# Proiect_v64.net
KiCad netlist of a schematic drawn in EAGLE
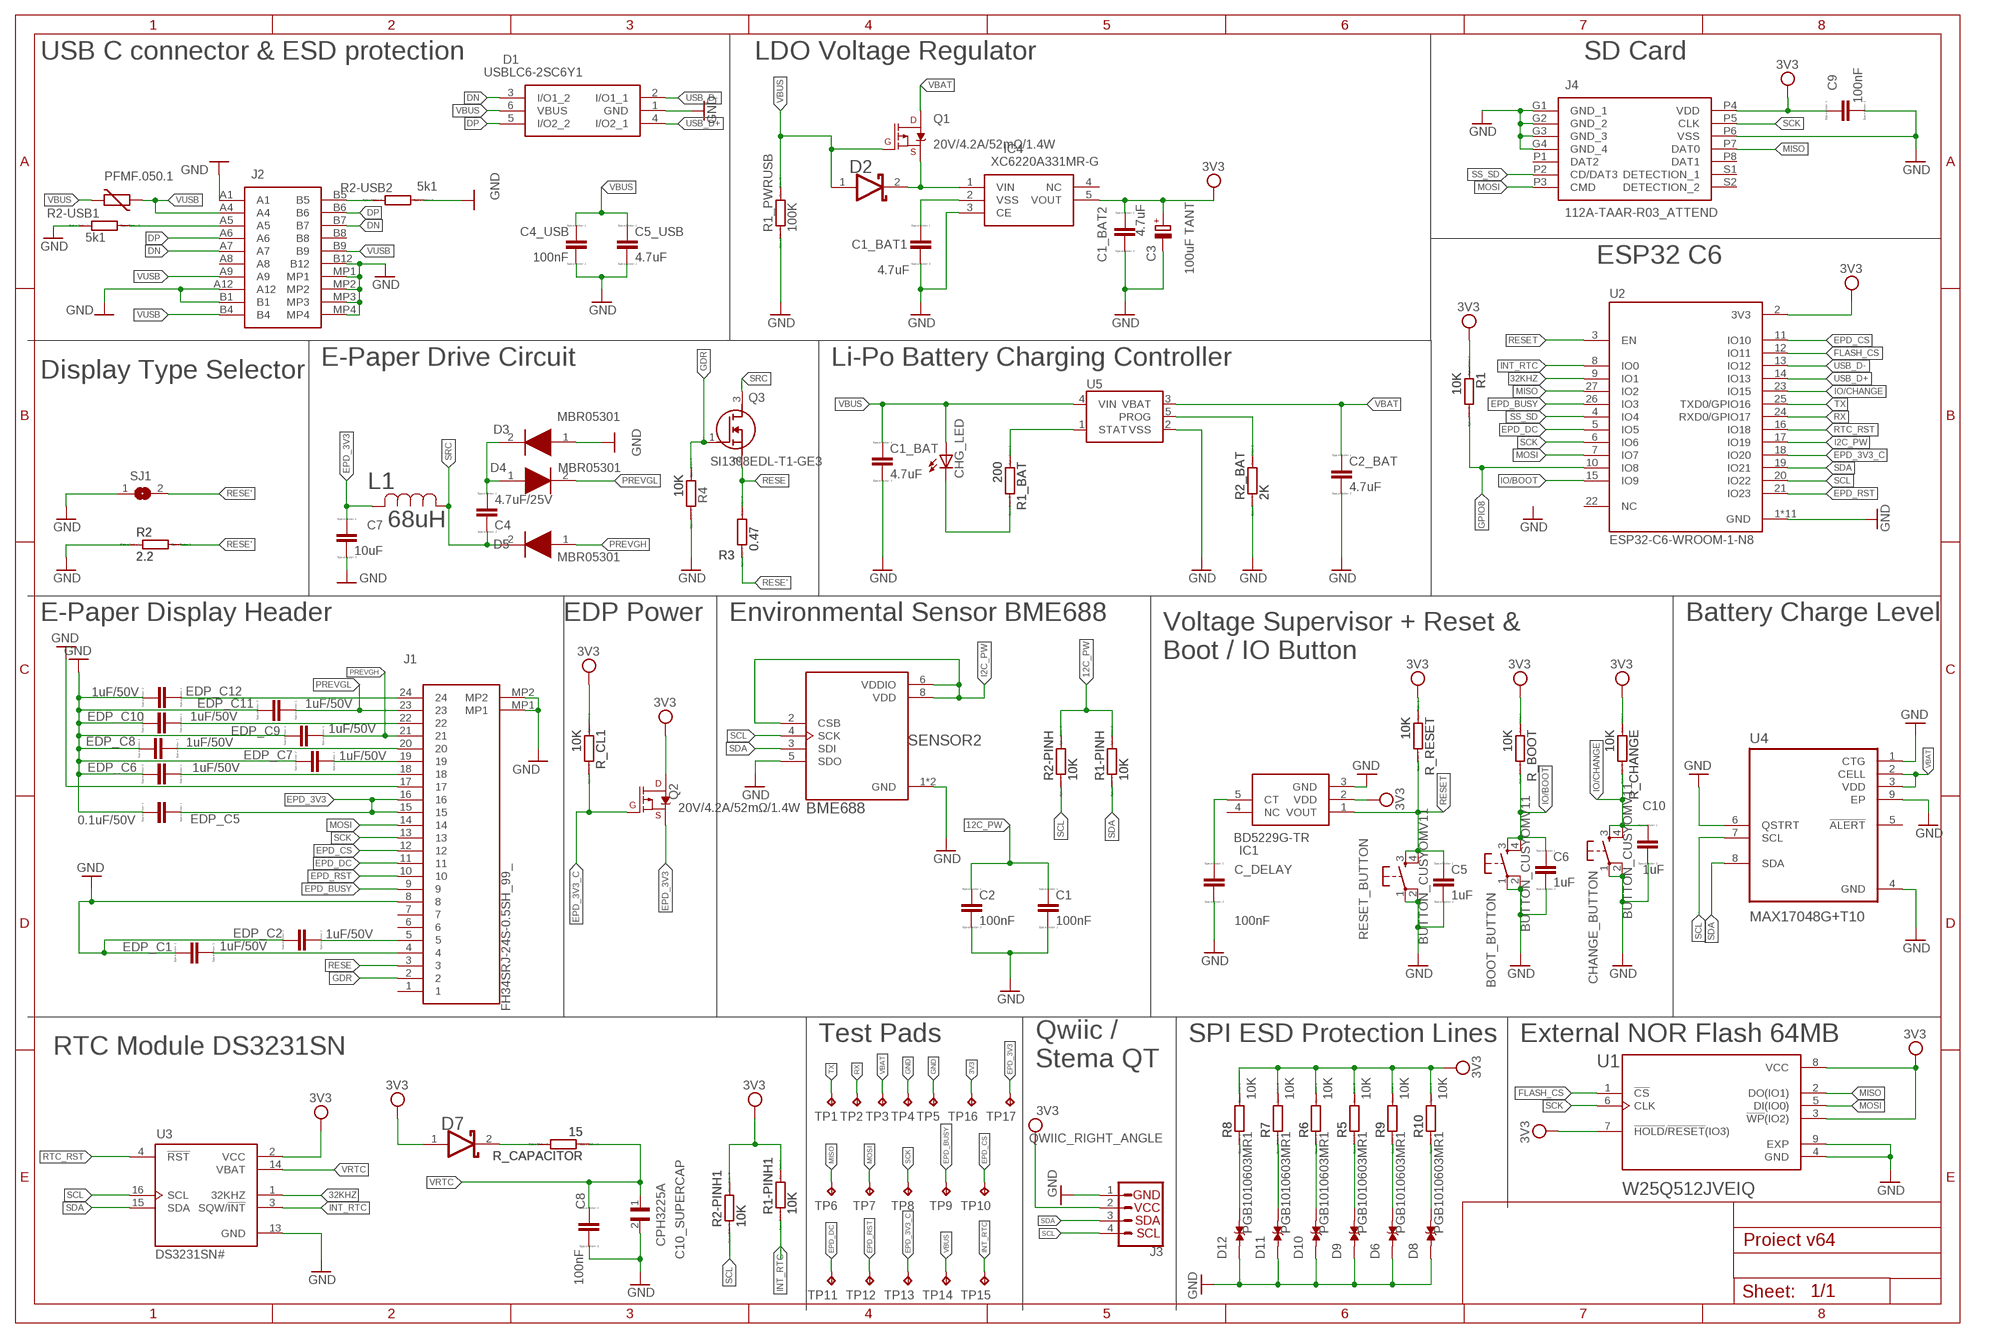
[diagram p0: schematic, sheet 1]

(export (version "E")
  (design (tool "Eeschema 10.0.6"))
  (components
    (comp (ref "BOOT_BUTTON")
      (value "BUTTON_CUSYOMV11")
      (footprint "eagle-import:MYBUTTON")
      (libsource (lib "eagle-import") (part "BUTTON_CUSYOMV11"))
    )
    (comp (ref "C1")
      (value "100nF")
      (footprint "eagle-import:ESP32_WROVER_EAGLE-LTSPICE_C0402")
      (libsource (lib "eagle-import") (part "ESP32_WROVER_EAGLE-LTSPICE_C"))
    )
    (comp (ref "C1_BAT")
      (value "4.7uF")
      (footprint "eagle-import:ESP32_WROVER_EAGLE-LTSPICE_C0402")
      (libsource (lib "eagle-import") (part "ESP32_WROVER_EAGLE-LTSPICE_C"))
    )
    (comp (ref "C1_BAT1")
      (value "4.7uF")
      (footprint "eagle-import:ESP32_WROVER_EAGLE-LTSPICE_C0402")
      (libsource (lib "eagle-import") (part "ESP32_WROVER_EAGLE-LTSPICE_C"))
    )
    (comp (ref "C1_BAT2")
      (value "4.7uF")
      (footprint "eagle-import:ESP32_WROVER_EAGLE-LTSPICE_C0402")
      (libsource (lib "eagle-import") (part "ESP32_WROVER_EAGLE-LTSPICE_C"))
    )
    (comp (ref "C2")
      (value "100nF")
      (footprint "eagle-import:ESP32_WROVER_EAGLE-LTSPICE_C0402")
      (libsource (lib "eagle-import") (part "ESP32_WROVER_EAGLE-LTSPICE_C"))
    )
    (comp (ref "C2_BAT")
      (value "4.7uF")
      (footprint "eagle-import:ESP32_WROVER_EAGLE-LTSPICE_C0402")
      (libsource (lib "eagle-import") (part "ESP32_WROVER_EAGLE-LTSPICE_C"))
    )
    (comp (ref "C3")
      (value "100uF TANT")
      (footprint "eagle-import:RCL_CT3528")
      (libsource (lib "eagle-import") (part "RCL_CPOL-EUCT3528"))
    )
    (comp (ref "C4")
      (value "4.7uF/25V")
      (footprint "eagle-import:ESP32_WROVER_EAGLE-LTSPICE_C0402")
      (libsource (lib "eagle-import") (part "ESP32_WROVER_EAGLE-LTSPICE_C"))
    )
    (comp (ref "C4_USB")
      (value "100nF")
      (footprint "eagle-import:ESP32_WROVER_EAGLE-LTSPICE_C0402")
      (libsource (lib "eagle-import") (part "ESP32_WROVER_EAGLE-LTSPICE_C"))
    )
    (comp (ref "C5")
      (value "1uF")
      (footprint "eagle-import:ESP32_WROVER_EAGLE-LTSPICE_C0402")
      (libsource (lib "eagle-import") (part "ESP32_WROVER_EAGLE-LTSPICE_C"))
    )
    (comp (ref "C5_USB")
      (value "4.7uF")
      (footprint "eagle-import:ESP32_WROVER_EAGLE-LTSPICE_C0402")
      (libsource (lib "eagle-import") (part "ESP32_WROVER_EAGLE-LTSPICE_C"))
    )
    (comp (ref "C6")
      (value "1uF")
      (footprint "eagle-import:ESP32_WROVER_EAGLE-LTSPICE_C0402")
      (libsource (lib "eagle-import") (part "ESP32_WROVER_EAGLE-LTSPICE_C"))
    )
    (comp (ref "C7")
      (value "10uF")
      (footprint "eagle-import:ESP32_WROVER_EAGLE-LTSPICE_C0402")
      (libsource (lib "eagle-import") (part "ESP32_WROVER_EAGLE-LTSPICE_C"))
    )
    (comp (ref "C8")
      (value "100nF")
      (footprint "eagle-import:ESP32_WROVER_EAGLE-LTSPICE_C0402")
      (libsource (lib "eagle-import") (part "ESP32_WROVER_EAGLE-LTSPICE_C"))
    )
    (comp (ref "C9")
      (value "100nF")
      (footprint "eagle-import:ESP32_WROVER_EAGLE-LTSPICE_C0402")
      (libsource (lib "eagle-import") (part "ESP32_WROVER_EAGLE-LTSPICE_C"))
    )
    (comp (ref "C10")
      (value "1uF")
      (footprint "eagle-import:ESP32_WROVER_EAGLE-LTSPICE_C0402")
      (libsource (lib "eagle-import") (part "ESP32_WROVER_EAGLE-LTSPICE_C"))
    )
    (comp (ref "C10_SUPERCAP")
      (value "CPH3225A")
      (footprint "eagle-import:CAPCP3225X100N")
      (fields (field (name "MF") "Seiko Instruments"))
      (libsource (lib "eagle-import") (part "CPH3225A"))
    )
    (comp (ref "CHANGE_BUTTON")
      (value "BUTTON_CUSYOMV11")
      (footprint "eagle-import:MYBUTTON")
      (libsource (lib "eagle-import") (part "BUTTON_CUSYOMV11"))
    )
    (comp (ref "CHG_LED")
      (value "1")
      (footprint "eagle-import:ADAFRUIT_CHIP-LED0603")
      (libsource (lib "eagle-import") (part "ADAFRUIT_LEDCHIP-LED0603"))
    )
    (comp (ref "C_DELAY")
      (value "100nF")
      (footprint "eagle-import:ESP32_WROVER_EAGLE-LTSPICE_C0402")
      (libsource (lib "eagle-import") (part "ESP32_WROVER_EAGLE-LTSPICE_C"))
    )
    (comp (ref "D1")
      (value "USBLC6-2SC6Y1")
      (footprint "eagle-import:SOT95P280X145-6N")
      (libsource (lib "eagle-import") (part "USBLC6-2SC6Y1"))
    )
    (comp (ref "D2")
      (value "ESP32_WROVER_AVX---SD0805S020S1R0_AVX_SD0805S020S1R0_0_0")
      (footprint "eagle-import:ESP32_WROVER_AVX---SD0805S020S1R0_AVX_SD0805S020S1R0_0")
      (libsource (lib "eagle-import") (part "ESP32_WROVER_AVX---SD0805S020S1R0_AVX_SD0805S020S1R0_0_0"))
    )
    (comp (ref "D3")
      (value "MBR05301")
      (footprint "eagle-import:SOD3716X135N")
      (libsource (lib "eagle-import") (part "MBR05301"))
    )
    (comp (ref "D4")
      (value "MBR05301")
      (footprint "eagle-import:SOD3716X135N")
      (libsource (lib "eagle-import") (part "MBR05301"))
    )
    (comp (ref "D5")
      (value "MBR05301")
      (footprint "eagle-import:SOD3716X135N")
      (libsource (lib "eagle-import") (part "MBR05301"))
    )
    (comp (ref "D6")
      (value "PGB1010603MR1")
      (footprint "eagle-import:DIOC1608X36N")
      (libsource (lib "eagle-import") (part "PGB1010603MR1"))
    )
    (comp (ref "D7")
      (value "SD805S020S1R0")
      (footprint "eagle-import:ESP32_WROVER_AVX---SD0805S020S1R0_AVX_SD0805S020S1R0_0")
      (libsource (lib "eagle-import") (part "ESP32_WROVER_AVX---SD0805S020S1R0_AVX_SD0805S020S1R0_0_0"))
    )
    (comp (ref "D8")
      (value "PGB1010603MR1")
      (footprint "eagle-import:DIOC1608X36N")
      (libsource (lib "eagle-import") (part "PGB1010603MR1"))
    )
    (comp (ref "D9")
      (value "PGB1010603MR1")
      (footprint "eagle-import:DIOC1608X36N")
      (libsource (lib "eagle-import") (part "PGB1010603MR1"))
    )
    (comp (ref "D10")
      (value "PGB1010603MR1")
      (footprint "eagle-import:DIOC1608X36N")
      (libsource (lib "eagle-import") (part "PGB1010603MR1"))
    )
    (comp (ref "D11")
      (value "PGB1010603MR1")
      (footprint "eagle-import:DIOC1608X36N")
      (libsource (lib "eagle-import") (part "PGB1010603MR1"))
    )
    (comp (ref "D12")
      (value "PGB1010603MR1")
      (footprint "eagle-import:DIOC1608X36N")
      (libsource (lib "eagle-import") (part "PGB1010603MR1"))
    )
    (comp (ref "EDP_C1")
      (value "1uF/50V")
      (footprint "eagle-import:ESP32_WROVER_EAGLE-LTSPICE_C0402")
      (libsource (lib "eagle-import") (part "ESP32_WROVER_EAGLE-LTSPICE_C"))
    )
    (comp (ref "EDP_C2")
      (value "1uF/50V")
      (footprint "eagle-import:ESP32_WROVER_EAGLE-LTSPICE_C0402")
      (libsource (lib "eagle-import") (part "ESP32_WROVER_EAGLE-LTSPICE_C"))
    )
    (comp (ref "EDP_C5")
      (value "0.1uF/50V")
      (footprint "eagle-import:ESP32_WROVER_EAGLE-LTSPICE_C0402")
      (libsource (lib "eagle-import") (part "ESP32_WROVER_EAGLE-LTSPICE_C"))
    )
    (comp (ref "EDP_C6")
      (value "1uF/50V")
      (footprint "eagle-import:ESP32_WROVER_EAGLE-LTSPICE_C0402")
      (libsource (lib "eagle-import") (part "ESP32_WROVER_EAGLE-LTSPICE_C"))
    )
    (comp (ref "EDP_C7")
      (value "1uF/50V")
      (footprint "eagle-import:ESP32_WROVER_EAGLE-LTSPICE_C0402")
      (libsource (lib "eagle-import") (part "ESP32_WROVER_EAGLE-LTSPICE_C"))
    )
    (comp (ref "EDP_C8")
      (value "1uF/50V")
      (footprint "eagle-import:ESP32_WROVER_EAGLE-LTSPICE_C0402")
      (libsource (lib "eagle-import") (part "ESP32_WROVER_EAGLE-LTSPICE_C"))
    )
    (comp (ref "EDP_C9")
      (value "1uF/50V")
      (footprint "eagle-import:ESP32_WROVER_EAGLE-LTSPICE_C0402")
      (libsource (lib "eagle-import") (part "ESP32_WROVER_EAGLE-LTSPICE_C"))
    )
    (comp (ref "EDP_C10")
      (value "1uF/50V")
      (footprint "eagle-import:ESP32_WROVER_EAGLE-LTSPICE_C0402")
      (libsource (lib "eagle-import") (part "ESP32_WROVER_EAGLE-LTSPICE_C"))
    )
    (comp (ref "EDP_C11")
      (value "1uF/50V")
      (footprint "eagle-import:ESP32_WROVER_EAGLE-LTSPICE_C0402")
      (libsource (lib "eagle-import") (part "ESP32_WROVER_EAGLE-LTSPICE_C"))
    )
    (comp (ref "EDP_C12")
      (value "1uF/50V")
      (footprint "eagle-import:ESP32_WROVER_EAGLE-LTSPICE_C0402")
      (libsource (lib "eagle-import") (part "ESP32_WROVER_EAGLE-LTSPICE_C"))
    )
    (comp (ref "IC1")
      (value "BD5229G-TR")
      (footprint "eagle-import:SOT95P280X125-5N")
      (fields (field (name "MOUSER_PART_NUMBER") "755-BD5229G-TR"))
      (libsource (lib "eagle-import") (part "BD5229G-TR"))
    )
    (comp (ref "IC4")
      (value "XC6220A331MR-G")
      (footprint "eagle-import:SOT95P280X120-5N")
      (fields (field (name "MOUSER_PART_NUMBER") "865-XC6220A331MR-G"))
      (libsource (lib "eagle-import") (part "XC6220A331MR-G"))
    )
    (comp (ref "J1")
      (value "FH34SRJ-24S-0.5SH_99_")
      (footprint "eagle-import:FH34SRJ24S05SH99")
      (fields
        (field (name "MANUFACTURER_PART_NUMBER") "FH34SRJ-24S-0.5SH(99)")
        (field (name "MOUSER_PART_NUMBER") "798-FH34SRJ24S05SH99")
      )
      (libsource (lib "eagle-import") (part "FH34SRJ-24S-0.5SH_99_"))
    )
    (comp (ref "J2")
      (value "SAMACSYS_PARTS_USB4110-GF-A")
      (footprint "eagle-import:SAMACSYS_PARTS_USB4110GFA")
      (fields
        (field (name "MANUFACTURER_PART_NUMBER") "USB4110-GF-A")
        (field (name "MOUSER_PART_NUMBER") "640-USB4110-GF-A")
      )
      (libsource (lib "eagle-import") (part "SAMACSYS_PARTS_USB4110-GF-A"))
    )
    (comp (ref "J3")
      (value "QWIIC_RIGHT_ANGLE")
      (footprint "eagle-import:JST04_1MM_RA")
      (libsource (lib "eagle-import") (part "QWIIC_CONNECTORJS-1MM"))
    )
    (comp (ref "J4")
      (value "112A-TAAR-R03_ATTEND")
      (footprint "eagle-import:112ATAARR03ATTEND")
      (fields (field (name "MANUFACTURER_PART_NUMBER") "112A-TAAR-R03 ATTEND"))
      (libsource (lib "eagle-import") (part "112A-TAAR-R03_ATTEND"))
    )
    (comp (ref "L1")
      (value "68uH")
      (footprint "eagle-import:IND_4828-WE-TPC_WRE")
      (fields
        (field (name "MANUFACTURER_PART_NUMBER") "744043680")
        (field (name "COPYRIGHT") "Copyright (C) 2024 Ultra Librarian. All rights reserved.")
      )
      (libsource (lib "eagle-import") (part "744043680IND_4828-WE-TPC_WRE"))
    )
    (comp (ref "PFMF.050.1")
      (value "ESP32C6_VARISTORCN1812")
      (footprint "eagle-import:ESP32C6_VARISTOR_CT_CN1812")
      (libsource (lib "eagle-import") (part "ESP32C6_VARISTORCN1812"))
    )
    (comp (ref "Q1")
      (value "20V/4.2A/52mΩ/1.4W")
      (footprint "eagle-import:ESP32_WROVER_SPARKFUN-DISCRETESEMI_SOT23-3")
      (libsource (lib "eagle-import") (part "ESP32_WROVER_SPARKFUN-DISCRETESEMI_MOSFET_PCH"))
    )
    (comp (ref "Q2")
      (value "20V/4.2A/52mΩ/1.4W")
      (footprint "eagle-import:ESP32_WROVER_SPARKFUN-DISCRETESEMI_SOT23-3")
      (libsource (lib "eagle-import") (part "ESP32_WROVER_SPARKFUN-DISCRETESEMI_MOSFET_PCH"))
    )
    (comp (ref "Q3")
      (value "SI1308EDL-T1-GE3")
      (footprint "eagle-import:SOT65P210X110-3N")
      (fields (field (name "MF") "Vishay Siliconix"))
      (libsource (lib "eagle-import") (part "SI1308EDL-T1-GE3"))
    )
    (comp (ref "R1")
      (value "10K")
      (footprint "eagle-import:ESP32_WROVER_EAGLE-LTSPICE_R0402")
      (libsource (lib "eagle-import") (part "ESP32_WROVER_EAGLE-LTSPICE_R"))
    )
    (comp (ref "R1-PINH")
      (value "10K")
      (footprint "eagle-import:ESP32_WROVER_EAGLE-LTSPICE_R0402")
      (libsource (lib "eagle-import") (part "ESP32_WROVER_EAGLE-LTSPICE_R"))
    )
    (comp (ref "R1-PINH1")
      (value "10K")
      (footprint "eagle-import:ESP32_WROVER_EAGLE-LTSPICE_R0402")
      (libsource (lib "eagle-import") (part "ESP32_WROVER_EAGLE-LTSPICE_R"))
    )
    (comp (ref "R1_BAT")
      (value "200")
      (footprint "eagle-import:ESP32_WROVER_EAGLE-LTSPICE_R0402")
      (libsource (lib "eagle-import") (part "ESP32_WROVER_EAGLE-LTSPICE_R"))
    )
    (comp (ref "R1_PWRUSB")
      (value "100K")
      (footprint "eagle-import:ESP32_WROVER_EAGLE-LTSPICE_R0402")
      (libsource (lib "eagle-import") (part "ESP32_WROVER_EAGLE-LTSPICE_R"))
    )
    (comp (ref "R2")
      (value "2.2")
      (footprint "eagle-import:ESP32_WROVER_EAGLE-LTSPICE_R0402")
      (libsource (lib "eagle-import") (part "ESP32_WROVER_EAGLE-LTSPICE_R"))
    )
    (comp (ref "R2-PINH")
      (value "10K")
      (footprint "eagle-import:ESP32_WROVER_EAGLE-LTSPICE_R0402")
      (libsource (lib "eagle-import") (part "ESP32_WROVER_EAGLE-LTSPICE_R"))
    )
    (comp (ref "R2-PINH1")
      (value "10K")
      (footprint "eagle-import:ESP32_WROVER_EAGLE-LTSPICE_R0402")
      (libsource (lib "eagle-import") (part "ESP32_WROVER_EAGLE-LTSPICE_R"))
    )
    (comp (ref "R2-USB1")
      (value "5k1")
      (footprint "eagle-import:ESP32_WROVER_EAGLE-LTSPICE_R0402")
      (libsource (lib "eagle-import") (part "ESP32_WROVER_EAGLE-LTSPICE_R"))
    )
    (comp (ref "R2-USB2")
      (value "5k1")
      (footprint "eagle-import:ESP32_WROVER_EAGLE-LTSPICE_R0402")
      (libsource (lib "eagle-import") (part "ESP32_WROVER_EAGLE-LTSPICE_R"))
    )
    (comp (ref "R2_BAT")
      (value "2K")
      (footprint "eagle-import:ESP32_WROVER_EAGLE-LTSPICE_R0402")
      (libsource (lib "eagle-import") (part "ESP32_WROVER_EAGLE-LTSPICE_R"))
    )
    (comp (ref "R3")
      (value "0.47")
      (footprint "eagle-import:ESP32_WROVER_EAGLE-LTSPICE_R0402")
      (libsource (lib "eagle-import") (part "ESP32_WROVER_EAGLE-LTSPICE_R"))
    )
    (comp (ref "R4")
      (value "10K")
      (footprint "eagle-import:ESP32_WROVER_EAGLE-LTSPICE_R0402")
      (libsource (lib "eagle-import") (part "ESP32_WROVER_EAGLE-LTSPICE_R"))
    )
    (comp (ref "R5")
      (value "10K")
      (footprint "eagle-import:ESP32_WROVER_EAGLE-LTSPICE_R0402")
      (libsource (lib "eagle-import") (part "ESP32_WROVER_EAGLE-LTSPICE_R"))
    )
    (comp (ref "R6")
      (value "10K")
      (footprint "eagle-import:ESP32_WROVER_EAGLE-LTSPICE_R0402")
      (libsource (lib "eagle-import") (part "ESP32_WROVER_EAGLE-LTSPICE_R"))
    )
    (comp (ref "R7")
      (value "10K")
      (footprint "eagle-import:ESP32_WROVER_EAGLE-LTSPICE_R0402")
      (libsource (lib "eagle-import") (part "ESP32_WROVER_EAGLE-LTSPICE_R"))
    )
    (comp (ref "R8")
      (value "10K")
      (footprint "eagle-import:ESP32_WROVER_EAGLE-LTSPICE_R0402")
      (libsource (lib "eagle-import") (part "ESP32_WROVER_EAGLE-LTSPICE_R"))
    )
    (comp (ref "R9")
      (value "10K")
      (footprint "eagle-import:ESP32_WROVER_EAGLE-LTSPICE_R0402")
      (libsource (lib "eagle-import") (part "ESP32_WROVER_EAGLE-LTSPICE_R"))
    )
    (comp (ref "R10")
      (value "10K")
      (footprint "eagle-import:ESP32_WROVER_EAGLE-LTSPICE_R0402")
      (libsource (lib "eagle-import") (part "ESP32_WROVER_EAGLE-LTSPICE_R"))
    )
    (comp (ref "RESET_BUTTON")
      (value "BUTTON_CUSYOMV11")
      (footprint "eagle-import:MYBUTTON")
      (libsource (lib "eagle-import") (part "BUTTON_CUSYOMV11"))
    )
    (comp (ref "R_BOOT")
      (value "10K")
      (footprint "eagle-import:ESP32_WROVER_EAGLE-LTSPICE_R0402")
      (libsource (lib "eagle-import") (part "ESP32_WROVER_EAGLE-LTSPICE_R"))
    )
    (comp (ref "R_CAPACITOR")
      (value "15")
      (footprint "eagle-import:ESP32_WROVER_EAGLE-LTSPICE_R0402")
      (libsource (lib "eagle-import") (part "ESP32_WROVER_EAGLE-LTSPICE_R"))
    )
    (comp (ref "R_CHANGE")
      (value "10K")
      (footprint "eagle-import:ESP32_WROVER_EAGLE-LTSPICE_R0402")
      (libsource (lib "eagle-import") (part "ESP32_WROVER_EAGLE-LTSPICE_R"))
    )
    (comp (ref "R_CL1")
      (value "10K")
      (footprint "eagle-import:ESP32_WROVER_EAGLE-LTSPICE_R0402")
      (libsource (lib "eagle-import") (part "ESP32_WROVER_EAGLE-LTSPICE_R"))
    )
    (comp (ref "R_RESET")
      (value "10K")
      (footprint "eagle-import:ESP32_WROVER_EAGLE-LTSPICE_R0402")
      (libsource (lib "eagle-import") (part "ESP32_WROVER_EAGLE-LTSPICE_R"))
    )
    (comp (ref "SENSOR2")
      (value "BME688")
      (footprint "eagle-import:ESP32_WROVER_BME680_PSON80P300X300X100-8N")
      (fields (field (name "MF") "Bosch Sensortec") (field (name "MP") "BME680"))
      (libsource (lib "eagle-import") (part "ESP32_WROVER_BME680_BME680"))
    )
    (comp (ref "SJ1") (value "1") (footprint "eagle-import:SJ") (libsource (lib "eagle-import") (part "SJ")))
    (comp (ref "TP1")
      (value "TP")
      (footprint "eagle-import:TP20R")
      (libsource (lib "eagle-import") (part "TP"))
    )
    (comp (ref "TP2")
      (value "TP")
      (footprint "eagle-import:TP20R")
      (libsource (lib "eagle-import") (part "TP"))
    )
    (comp (ref "TP3")
      (value "TP")
      (footprint "eagle-import:TP20R")
      (libsource (lib "eagle-import") (part "TP"))
    )
    (comp (ref "TP4")
      (value "TP")
      (footprint "eagle-import:TP20R")
      (libsource (lib "eagle-import") (part "TP"))
    )
    (comp (ref "TP5")
      (value "TP")
      (footprint "eagle-import:TP20R")
      (libsource (lib "eagle-import") (part "TP"))
    )
    (comp (ref "TP6")
      (value "TP")
      (footprint "eagle-import:TP20R")
      (libsource (lib "eagle-import") (part "TP"))
    )
    (comp (ref "TP7")
      (value "TP")
      (footprint "eagle-import:TP20R")
      (libsource (lib "eagle-import") (part "TP"))
    )
    (comp (ref "TP8")
      (value "TP")
      (footprint "eagle-import:TP20R")
      (libsource (lib "eagle-import") (part "TP"))
    )
    (comp (ref "TP9")
      (value "TP")
      (footprint "eagle-import:TP20R")
      (libsource (lib "eagle-import") (part "TP"))
    )
    (comp (ref "TP10")
      (value "TP")
      (footprint "eagle-import:TP20R")
      (libsource (lib "eagle-import") (part "TP"))
    )
    (comp (ref "TP11")
      (value "TP")
      (footprint "eagle-import:TP20R")
      (libsource (lib "eagle-import") (part "TP"))
    )
    (comp (ref "TP12")
      (value "TP")
      (footprint "eagle-import:TP20R")
      (libsource (lib "eagle-import") (part "TP"))
    )
    (comp (ref "TP13")
      (value "TP")
      (footprint "eagle-import:TP20R")
      (libsource (lib "eagle-import") (part "TP"))
    )
    (comp (ref "TP14")
      (value "TP")
      (footprint "eagle-import:TP20R")
      (libsource (lib "eagle-import") (part "TP"))
    )
    (comp (ref "TP15")
      (value "TP")
      (footprint "eagle-import:TP20R")
      (libsource (lib "eagle-import") (part "TP"))
    )
    (comp (ref "TP16")
      (value "TP")
      (footprint "eagle-import:TP20R")
      (libsource (lib "eagle-import") (part "TP"))
    )
    (comp (ref "TP17")
      (value "TP")
      (footprint "eagle-import:TP20R")
      (libsource (lib "eagle-import") (part "TP"))
    )
    (comp (ref "U1")
      (value "W25Q512JVEIQ")
      (footprint "eagle-import:SON127P600X800X80-9N")
      (fields (field (name "MF") "Winbond Electronics"))
      (libsource (lib "eagle-import") (part "W25Q512JVEIQ"))
    )
    (comp (ref "U2")
      (value "ESP32-C6-WROOM-1-N8")
      (footprint "eagle-import:XCVR_ESP32-C6-WROOM-1-N8")
      (fields (field (name "MF") "Espressif Systems"))
      (libsource (lib "eagle-import") (part "ESP32-C6-WROOM-1-N8"))
    )
    (comp (ref "U3")
      (value "DS3231SN#")
      (footprint "eagle-import:SOIC127P1032X265-16N")
      (fields (field (name "MF") "Analog Devices"))
      (libsource (lib "eagle-import") (part "DS3231SN#"))
    )
    (comp (ref "U4")
      (value "MAX17048G+T10")
      (footprint "eagle-import:SON50P200X200X80-9N")
      (fields (field (name "MF") "Analog Devices"))
      (libsource (lib "eagle-import") (part "MAX17048G+T10"))
    )
    (comp (ref "U5")
      (value "MCP73831")
      (footprint "eagle-import:ESP32_WROVER_SPARKFUN-IC-POWER_SOT23-5")
      (libsource (lib "eagle-import") (part "ESP32_WROVER_SPARKFUN-IC-POWER_MCP73831"))
    )
  )
  (nets
    (net (code "1") (name "3V3") (class "Default")
      (node (ref "C1_BAT2") (pin "1") (pinfunction "1_1") (pintype "passive"))
      (node (ref "C3") (pin "+") (pinfunction "+_+") (pintype "passive"))
      (node (ref "C9") (pin "1") (pinfunction "1_1") (pintype "passive"))
      (node (ref "D7") (pin "1") (pinfunction "ANODE_1") (pintype "bidirectional"))
      (node (ref "IC1") (pin "2") (pinfunction "VDD_2") (pintype "bidirectional"))
      (node (ref "IC4") (pin "5") (pinfunction "VOUT_5") (pintype "bidirectional"))
      (node (ref "J3") (pin "2") (pinfunction "2_2") (pintype "power_in"))
      (node (ref "J4") (pin "P4") (pinfunction "VDD_P4") (pintype "bidirectional"))
      (node (ref "Q2") (pin "1") (pinfunction "D_1") (pintype "bidirectional"))
      (node (ref "R1") (pin "1") (pinfunction "1_1") (pintype "passive"))
      (node (ref "R1-PINH1") (pin "2") (pinfunction "2_2") (pintype "passive"))
      (node (ref "R10") (pin "2") (pinfunction "2_2") (pintype "passive"))
      (node (ref "R2-PINH1") (pin "2") (pinfunction "2_2") (pintype "passive"))
      (node (ref "R5") (pin "2") (pinfunction "2_2") (pintype "passive"))
      (node (ref "R6") (pin "2") (pinfunction "2_2") (pintype "passive"))
      (node (ref "R7") (pin "2") (pinfunction "2_2") (pintype "passive"))
      (node (ref "R8") (pin "2") (pinfunction "2_2") (pintype "passive"))
      (node (ref "R9") (pin "2") (pinfunction "2_2") (pintype "passive"))
      (node (ref "R_BOOT") (pin "1") (pinfunction "1_1") (pintype "passive"))
      (node (ref "R_CHANGE") (pin "1") (pinfunction "1_1") (pintype "passive"))
      (node (ref "R_CL1") (pin "1") (pinfunction "1_1") (pintype "passive"))
      (node (ref "R_RESET") (pin "1") (pinfunction "1_1") (pintype "passive"))
      (node (ref "TP16") (pin "TP") (pinfunction "TP_TP") (pintype "input"))
      (node (ref "U1") (pin "3") (pinfunction "~{WP}(IO2)_3") (pintype "bidirectional"))
      (node (ref "U1") (pin "7") (pinfunction "~{HOLD}/~{RESET}(IO3)_7") (pintype "bidirectional"))
      (node (ref "U1") (pin "8") (pinfunction "VCC_8") (pintype "power_in"))
      (node (ref "U2") (pin "2") (pinfunction "3V3_2") (pintype "power_in"))
      (node (ref "U3") (pin "2") (pinfunction "VCC_2") (pintype "power_in"))
    )
    (net (code "2") (name "12C_PW") (class "Default")
      (node (ref "C1") (pin "1") (pinfunction "1_1") (pintype "passive"))
      (node (ref "C2") (pin "1") (pinfunction "1_1") (pintype "passive"))
      (node (ref "R1-PINH") (pin "2") (pinfunction "2_2") (pintype "passive"))
      (node (ref "R2-PINH") (pin "2") (pinfunction "2_2") (pintype "passive"))
    )
    (net (code "3") (name "32KHZ") (class "Default")
      (node (ref "U2") (pin "9") (pinfunction "IO1_9") (pintype "bidirectional"))
      (node (ref "U3") (pin "1") (pinfunction "32KHZ_1") (pintype "output"))
    )
    (net (code "4") (name "DN") (class "Default")
      (node (ref "D1") (pin "3") (pinfunction "I/O1_2_3") (pintype "bidirectional"))
      (node (ref "J2") (pin "A7") (pinfunction "A7_A7") (pintype "bidirectional"))
      (node (ref "J2") (pin "B7") (pinfunction "B7_B7") (pintype "bidirectional"))
    )
    (net (code "5") (name "DP") (class "Default")
      (node (ref "D1") (pin "5") (pinfunction "I/O2_2_5") (pintype "bidirectional"))
      (node (ref "J2") (pin "A6") (pinfunction "A6_A6") (pintype "bidirectional"))
      (node (ref "J2") (pin "B6") (pinfunction "B6_B6") (pintype "bidirectional"))
    )
    (net (code "6") (name "EPD_3V3") (class "Default")
      (node (ref "C7") (pin "1") (pinfunction "1_1") (pintype "passive"))
      (node (ref "EDP_C5") (pin "1") (pinfunction "1_1") (pintype "passive"))
      (node (ref "J1") (pin "15") (pinfunction "15_15") (pintype "bidirectional"))
      (node (ref "J1") (pin "16") (pinfunction "16_16") (pintype "bidirectional"))
      (node (ref "L1") (pin "2") (pinfunction "2_2") (pintype "passive"))
      (node (ref "Q2") (pin "3") (pinfunction "S_3") (pintype "bidirectional"))
      (node (ref "TP17") (pin "TP") (pinfunction "TP_TP") (pintype "input"))
    )
    (net (code "7") (name "EPD_3V3_C") (class "Default")
      (node (ref "Q2") (pin "2") (pinfunction "G_2") (pintype "bidirectional"))
      (node (ref "R_CL1") (pin "2") (pinfunction "2_2") (pintype "passive"))
      (node (ref "TP13") (pin "TP") (pinfunction "TP_TP") (pintype "input"))
      (node (ref "U2") (pin "18") (pinfunction "IO20_18") (pintype "bidirectional"))
    )
    (net (code "8") (name "EPD_BUSY") (class "Default")
      (node (ref "J1") (pin "9") (pinfunction "9_9") (pintype "bidirectional"))
      (node (ref "TP9") (pin "TP") (pinfunction "TP_TP") (pintype "input"))
      (node (ref "U2") (pin "26") (pinfunction "IO3_26") (pintype "bidirectional"))
    )
    (net (code "9") (name "EPD_CS") (class "Default")
      (node (ref "J1") (pin "12") (pinfunction "12_12") (pintype "bidirectional"))
      (node (ref "TP10") (pin "TP") (pinfunction "TP_TP") (pintype "input"))
      (node (ref "U2") (pin "11") (pinfunction "IO10_11") (pintype "bidirectional"))
    )
    (net (code "10") (name "EPD_DC") (class "Default")
      (node (ref "J1") (pin "11") (pinfunction "11_11") (pintype "bidirectional"))
      (node (ref "TP11") (pin "TP") (pinfunction "TP_TP") (pintype "input"))
      (node (ref "U2") (pin "5") (pinfunction "IO5_5") (pintype "bidirectional"))
    )
    (net (code "11") (name "EPD_RST") (class "Default")
      (node (ref "J1") (pin "10") (pinfunction "10_10") (pintype "bidirectional"))
      (node (ref "TP12") (pin "TP") (pinfunction "TP_TP") (pintype "input"))
      (node (ref "U2") (pin "21") (pinfunction "IO23_21") (pintype "bidirectional"))
    )
    (net (code "12") (name "FLASH_CS") (class "Default")
      (node (ref "U1") (pin "1") (pinfunction "~{CS}_1") (pintype "input"))
      (node (ref "U2") (pin "12") (pinfunction "IO11_12") (pintype "bidirectional"))
    )
    (net (code "13") (name "GDR") (class "Default")
      (node (ref "J1") (pin "2") (pinfunction "2_2") (pintype "bidirectional"))
      (node (ref "Q3") (pin "1") (pinfunction "G_1") (pintype "bidirectional"))
      (node (ref "R4") (pin "1") (pinfunction "1_1") (pintype "passive"))
    )
    (net (code "14") (name "GND") (class "Default")
      (node (ref "BOOT_BUTTON") (pin "1") (pinfunction "1_1") (pintype "passive"))
      (node (ref "BOOT_BUTTON") (pin "2") (pinfunction "2_2") (pintype "passive"))
      (node (ref "C1") (pin "2") (pinfunction "2_2") (pintype "passive"))
      (node (ref "C10") (pin "2") (pinfunction "2_2") (pintype "passive"))
      (node (ref "C10_SUPERCAP") (pin "2") (pinfunction "2_2") (pintype "passive"))
      (node (ref "C1_BAT") (pin "2") (pinfunction "2_2") (pintype "passive"))
      (node (ref "C1_BAT1") (pin "2") (pinfunction "2_2") (pintype "passive"))
      (node (ref "C1_BAT2") (pin "2") (pinfunction "2_2") (pintype "passive"))
      (node (ref "C2") (pin "2") (pinfunction "2_2") (pintype "passive"))
      (node (ref "C2_BAT") (pin "2") (pinfunction "2_2") (pintype "passive"))
      (node (ref "C3") (pin "-") (pinfunction "-_-") (pintype "passive"))
      (node (ref "C4_USB") (pin "2") (pinfunction "2_2") (pintype "passive"))
      (node (ref "C5") (pin "2") (pinfunction "2_2") (pintype "passive"))
      (node (ref "C5_USB") (pin "2") (pinfunction "2_2") (pintype "passive"))
      (node (ref "C6") (pin "2") (pinfunction "2_2") (pintype "passive"))
      (node (ref "C7") (pin "2") (pinfunction "2_2") (pintype "passive"))
      (node (ref "C8") (pin "2") (pinfunction "2_2") (pintype "passive"))
      (node (ref "C9") (pin "2") (pinfunction "2_2") (pintype "passive"))
      (node (ref "CHANGE_BUTTON") (pin "1") (pinfunction "1_1") (pintype "passive"))
      (node (ref "CHANGE_BUTTON") (pin "2") (pinfunction "2_2") (pintype "passive"))
      (node (ref "C_DELAY") (pin "2") (pinfunction "2_2") (pintype "passive"))
      (node (ref "D1") (pin "1") (pinfunction "GND_1") (pintype "bidirectional"))
      (node (ref "D10") (pin "1") (pinfunction "1_1") (pintype "passive"))
      (node (ref "D11") (pin "1") (pinfunction "1_1") (pintype "passive"))
      (node (ref "D12") (pin "1") (pinfunction "1_1") (pintype "passive"))
      (node (ref "D3") (pin "1") (pinfunction "A_1") (pintype "bidirectional"))
      (node (ref "D6") (pin "1") (pinfunction "1_1") (pintype "passive"))
      (node (ref "D8") (pin "1") (pinfunction "1_1") (pintype "passive"))
      (node (ref "D9") (pin "1") (pinfunction "1_1") (pintype "passive"))
      (node (ref "EDP_C1") (pin "2") (pinfunction "2_2") (pintype "passive"))
      (node (ref "EDP_C10") (pin "2") (pinfunction "2_2") (pintype "passive"))
      (node (ref "EDP_C11") (pin "2") (pinfunction "2_2") (pintype "passive"))
      (node (ref "EDP_C12") (pin "2") (pinfunction "2_2") (pintype "passive"))
      (node (ref "EDP_C2") (pin "2") (pinfunction "2_2") (pintype "passive"))
      (node (ref "EDP_C5") (pin "2") (pinfunction "2_2") (pintype "passive"))
      (node (ref "EDP_C6") (pin "2") (pinfunction "2_2") (pintype "passive"))
      (node (ref "EDP_C7") (pin "2") (pinfunction "2_2") (pintype "passive"))
      (node (ref "EDP_C8") (pin "2") (pinfunction "2_2") (pintype "passive"))
      (node (ref "EDP_C9") (pin "2") (pinfunction "2_2") (pintype "passive"))
      (node (ref "IC1") (pin "3") (pinfunction "GND_3") (pintype "bidirectional"))
      (node (ref "IC4") (pin "3") (pinfunction "CE_3") (pintype "bidirectional"))
      (node (ref "J1") (pin "17") (pinfunction "17_17") (pintype "bidirectional"))
      (node (ref "J1") (pin "8") (pinfunction "8_8") (pintype "bidirectional"))
      (node (ref "J1") (pin "MP1") (pinfunction "MP1_MP1") (pintype "bidirectional"))
      (node (ref "J1") (pin "MP2") (pinfunction "MP2_MP2") (pintype "bidirectional"))
      (node (ref "J2") (pin "A1") (pinfunction "A1_A1") (pintype "bidirectional"))
      (node (ref "J2") (pin "A12") (pinfunction "A12_A12") (pintype "bidirectional"))
      (node (ref "J2") (pin "B1") (pinfunction "B1_B1") (pintype "bidirectional"))
      (node (ref "J2") (pin "B12") (pinfunction "B12_B12") (pintype "bidirectional"))
      (node (ref "J2") (pin "MP1") (pinfunction "MP1_MP1") (pintype "bidirectional"))
      (node (ref "J2") (pin "MP2") (pinfunction "MP2_MP2") (pintype "bidirectional"))
      (node (ref "J2") (pin "MP3") (pinfunction "MP3_MP3") (pintype "bidirectional"))
      (node (ref "J2") (pin "MP4") (pinfunction "MP4_MP4") (pintype "bidirectional"))
      (node (ref "J3") (pin "1") (pinfunction "1_1") (pintype "power_in"))
      (node (ref "J4") (pin "G1") (pinfunction "GND_1_G1") (pintype "bidirectional"))
      (node (ref "J4") (pin "G2") (pinfunction "GND_2_G2") (pintype "bidirectional"))
      (node (ref "J4") (pin "G3") (pinfunction "GND_3_G3") (pintype "bidirectional"))
      (node (ref "J4") (pin "G4") (pinfunction "GND_4_G4") (pintype "bidirectional"))
      (node (ref "J4") (pin "P6") (pinfunction "VSS_P6") (pintype "bidirectional"))
      (node (ref "R1_PWRUSB") (pin "1") (pinfunction "1_1") (pintype "passive"))
      (node (ref "R2") (pin "1") (pinfunction "1_1") (pintype "passive"))
      (node (ref "R2-USB1") (pin "1") (pinfunction "1_1") (pintype "passive"))
      (node (ref "R2-USB2") (pin "2") (pinfunction "2_2") (pintype "passive"))
      (node (ref "R2_BAT") (pin "1") (pinfunction "1_1") (pintype "passive"))
      (node (ref "R4") (pin "2") (pinfunction "2_2") (pintype "passive"))
      (node (ref "RESET_BUTTON") (pin "1") (pinfunction "1_1") (pintype "passive"))
      (node (ref "RESET_BUTTON") (pin "2") (pinfunction "2_2") (pintype "passive"))
      (node (ref "SENSOR2") (pin "1") (pinfunction "GND_1") (pintype "power_in"))
      (node (ref "SENSOR2") (pin "5") (pinfunction "SDO_5") (pintype "bidirectional"))
      (node (ref "SENSOR2") (pin "7") (pinfunction "GND_7") (pintype "power_in"))
      (node (ref "SJ1") (pin "1") (pinfunction "1_1") (pintype "passive"))
      (node (ref "TP4") (pin "TP") (pinfunction "TP_TP") (pintype "input"))
      (node (ref "TP5") (pin "TP") (pinfunction "TP_TP") (pintype "input"))
      (node (ref "U1") (pin "4") (pinfunction "GND_4") (pintype "power_in"))
      (node (ref "U1") (pin "9") (pinfunction "EXP_9") (pintype "passive"))
      (node (ref "U2") (pin "1") (pinfunction "GND_1") (pintype "power_in"))
      (node (ref "U2") (pin "28") (pinfunction "GND_28") (pintype "power_in"))
      (node (ref "U2") (pin "29_1") (pinfunction "GND_29_1") (pintype "power_in"))
      (node (ref "U2") (pin "29_2") (pinfunction "GND_29_2") (pintype "power_in"))
      (node (ref "U2") (pin "29_3") (pinfunction "GND_29_3") (pintype "power_in"))
      (node (ref "U2") (pin "29_4") (pinfunction "GND_29_4") (pintype "power_in"))
      (node (ref "U2") (pin "29_5") (pinfunction "GND_29_5") (pintype "power_in"))
      (node (ref "U2") (pin "29_6") (pinfunction "GND_29_6") (pintype "power_in"))
      (node (ref "U2") (pin "29_7") (pinfunction "GND_29_7") (pintype "power_in"))
      (node (ref "U2") (pin "29_8") (pinfunction "GND_29_8") (pintype "power_in"))
      (node (ref "U2") (pin "29_9") (pinfunction "GND_29_9") (pintype "power_in"))
      (node (ref "U3") (pin "13") (pinfunction "GND_13") (pintype "power_in"))
      (node (ref "U4") (pin "1") (pinfunction "CTG_1") (pintype "power_in"))
      (node (ref "U4") (pin "4") (pinfunction "GND_4") (pintype "power_in"))
      (node (ref "U4") (pin "6") (pinfunction "QSTRT_6") (pintype "input"))
      (node (ref "U4") (pin "9") (pinfunction "EP_9") (pintype "power_in"))
      (node (ref "U5") (pin "2") (pinfunction "VSS_2") (pintype "power_in"))
    )
    (net (code "15") (name "GPIO8") (class "Default")
      (node (ref "R1") (pin "2") (pinfunction "2_2") (pintype "passive"))
      (node (ref "U2") (pin "10") (pinfunction "IO8_10") (pintype "bidirectional"))
    )
    (net (code "16") (name "I2C_PW") (class "Default")
      (node (ref "SENSOR2") (pin "2") (pinfunction "CSB_2") (pintype "input"))
      (node (ref "SENSOR2") (pin "6") (pinfunction "VDDIO_6") (pintype "power_in"))
      (node (ref "SENSOR2") (pin "8") (pinfunction "VDD_8") (pintype "power_in"))
      (node (ref "U2") (pin "17") (pinfunction "IO19_17") (pintype "bidirectional"))
    )
    (net (code "17") (name "INT_RTC") (class "Default")
      (node (ref "R1-PINH1") (pin "1") (pinfunction "1_1") (pintype "passive"))
      (node (ref "TP15") (pin "TP") (pinfunction "TP_TP") (pintype "input"))
      (node (ref "U2") (pin "8") (pinfunction "IO0_8") (pintype "bidirectional"))
      (node (ref "U3") (pin "3") (pinfunction "SQW/~{INT}_3") (pintype "output"))
    )
    (net (code "18") (name "IO{slash}BOOT") (class "Default")
      (node (ref "BOOT_BUTTON") (pin "3") (pinfunction "3_3") (pintype "passive"))
      (node (ref "BOOT_BUTTON") (pin "4") (pinfunction "4_4") (pintype "passive"))
      (node (ref "C6") (pin "1") (pinfunction "1_1") (pintype "passive"))
      (node (ref "R_BOOT") (pin "2") (pinfunction "2_2") (pintype "passive"))
      (node (ref "U2") (pin "15") (pinfunction "IO9_15") (pintype "bidirectional"))
    )
    (net (code "19") (name "IO{slash}CHANGE") (class "Default")
      (node (ref "C10") (pin "1") (pinfunction "1_1") (pintype "passive"))
      (node (ref "CHANGE_BUTTON") (pin "3") (pinfunction "3_3") (pintype "passive"))
      (node (ref "CHANGE_BUTTON") (pin "4") (pinfunction "4_4") (pintype "passive"))
      (node (ref "R_CHANGE") (pin "2") (pinfunction "2_2") (pintype "passive"))
      (node (ref "U2") (pin "23") (pinfunction "IO15_23") (pintype "bidirectional"))
    )
    (net (code "20") (name "MISO") (class "Default")
      (node (ref "J4") (pin "P7") (pinfunction "DAT0_P7") (pintype "bidirectional"))
      (node (ref "TP6") (pin "TP") (pinfunction "TP_TP") (pintype "input"))
      (node (ref "U1") (pin "2") (pinfunction "DO(IO1)_2") (pintype "bidirectional"))
      (node (ref "U2") (pin "27") (pinfunction "IO2_27") (pintype "bidirectional"))
    )
    (net (code "21") (name "MOSI") (class "Default")
      (node (ref "J1") (pin "14") (pinfunction "14_14") (pintype "bidirectional"))
      (node (ref "J4") (pin "P3") (pinfunction "CMD_P3") (pintype "bidirectional"))
      (node (ref "TP7") (pin "TP") (pinfunction "TP_TP") (pintype "input"))
      (node (ref "U1") (pin "5") (pinfunction "DI(IO0)_5") (pintype "bidirectional"))
      (node (ref "U2") (pin "7") (pinfunction "IO7_7") (pintype "bidirectional"))
    )
    (net (code "22") (name "Net-(CHG_LED-PadC)") (class "Default")
      (node (ref "CHG_LED") (pin "C") (pinfunction "C_C") (pintype "passive"))
      (node (ref "R1_BAT") (pin "2") (pinfunction "2_2") (pintype "passive"))
    )
    (net (code "23") (name "Net-(D2-CATHODE)") (class "Default")
      (node (ref "D2") (pin "2") (pinfunction "CATHODE_2") (pintype "bidirectional"))
      (node (ref "IC4") (pin "1") (pinfunction "VIN_1") (pintype "bidirectional"))
      (node (ref "Q1") (pin "3") (pinfunction "S_3") (pintype "bidirectional"))
    )
    (net (code "24") (name "Net-(D3-K)") (class "Default")
      (node (ref "C4") (pin "1") (pinfunction "1_1") (pintype "passive"))
      (node (ref "D3") (pin "2") (pinfunction "K_2") (pintype "bidirectional"))
      (node (ref "D4") (pin "1") (pinfunction "A_1") (pintype "bidirectional"))
    )
    (net (code "25") (name "Net-(D6-Pad2)") (class "Default")
      (node (ref "D6") (pin "2") (pinfunction "2_2") (pintype "passive"))
      (node (ref "R9") (pin "1") (pinfunction "1_1") (pintype "passive"))
    )
    (net (code "26") (name "Net-(D7-CATHODE)") (class "Default")
      (node (ref "D7") (pin "2") (pinfunction "CATHODE_2") (pintype "bidirectional"))
      (node (ref "R_CAPACITOR") (pin "2") (pinfunction "2_2") (pintype "passive"))
    )
    (net (code "27") (name "Net-(D8-Pad2)") (class "Default")
      (node (ref "D8") (pin "2") (pinfunction "2_2") (pintype "passive"))
      (node (ref "R10") (pin "1") (pinfunction "1_1") (pintype "passive"))
    )
    (net (code "28") (name "Net-(D9-Pad2)") (class "Default")
      (node (ref "D9") (pin "2") (pinfunction "2_2") (pintype "passive"))
      (node (ref "R5") (pin "1") (pinfunction "1_1") (pintype "passive"))
    )
    (net (code "29") (name "Net-(D10-Pad2)") (class "Default")
      (node (ref "D10") (pin "2") (pinfunction "2_2") (pintype "passive"))
      (node (ref "R6") (pin "1") (pinfunction "1_1") (pintype "passive"))
    )
    (net (code "30") (name "Net-(D11-Pad2)") (class "Default")
      (node (ref "D11") (pin "2") (pinfunction "2_2") (pintype "passive"))
      (node (ref "R7") (pin "1") (pinfunction "1_1") (pintype "passive"))
    )
    (net (code "31") (name "Net-(D12-Pad2)") (class "Default")
      (node (ref "D12") (pin "2") (pinfunction "2_2") (pintype "passive"))
      (node (ref "R8") (pin "1") (pinfunction "1_1") (pintype "passive"))
    )
    (net (code "32") (name "Net-(EDP_C1-Pad1)") (class "Default")
      (node (ref "EDP_C1") (pin "1") (pinfunction "1_1") (pintype "passive"))
      (node (ref "J1") (pin "4") (pinfunction "4_4") (pintype "bidirectional"))
    )
    (net (code "33") (name "Net-(EDP_C2-Pad1)") (class "Default")
      (node (ref "EDP_C2") (pin "1") (pinfunction "1_1") (pintype "passive"))
      (node (ref "J1") (pin "5") (pinfunction "5_5") (pintype "bidirectional"))
    )
    (net (code "34") (name "Net-(EDP_C6-Pad1)") (class "Default")
      (node (ref "EDP_C6") (pin "1") (pinfunction "1_1") (pintype "passive"))
      (node (ref "J1") (pin "18") (pinfunction "18_18") (pintype "bidirectional"))
    )
    (net (code "35") (name "Net-(EDP_C7-Pad1)") (class "Default")
      (node (ref "EDP_C7") (pin "1") (pinfunction "1_1") (pintype "passive"))
      (node (ref "J1") (pin "19") (pinfunction "19_19") (pintype "bidirectional"))
    )
    (net (code "36") (name "Net-(EDP_C8-Pad1)") (class "Default")
      (node (ref "EDP_C8") (pin "1") (pinfunction "1_1") (pintype "passive"))
      (node (ref "J1") (pin "20") (pinfunction "20_20") (pintype "bidirectional"))
    )
    (net (code "37") (name "Net-(EDP_C10-Pad1)") (class "Default")
      (node (ref "EDP_C10") (pin "1") (pinfunction "1_1") (pintype "passive"))
      (node (ref "J1") (pin "22") (pinfunction "22_22") (pintype "bidirectional"))
    )
    (net (code "38") (name "Net-(EDP_C12-Pad1)") (class "Default")
      (node (ref "EDP_C12") (pin "1") (pinfunction "1_1") (pintype "passive"))
      (node (ref "J1") (pin "24") (pinfunction "24_24") (pintype "bidirectional"))
    )
    (net (code "39") (name "Net-(IC1-CT)") (class "Default")
      (node (ref "C_DELAY") (pin "1") (pinfunction "1_1") (pintype "passive"))
      (node (ref "IC1") (pin "5") (pinfunction "CT_5") (pintype "bidirectional"))
    )
    (net (code "40") (name "Net-(IC4-VSS)") (class "Default")
      (node (ref "C1_BAT1") (pin "1") (pinfunction "1_1") (pintype "passive"))
      (node (ref "IC4") (pin "2") (pinfunction "VSS_2") (pintype "bidirectional"))
    )
    (net (code "41") (name "Net-(J2-PadA5)") (class "Default")
      (node (ref "J2") (pin "A5") (pinfunction "A5_A5") (pintype "bidirectional"))
      (node (ref "R2-USB1") (pin "2") (pinfunction "2_2") (pintype "passive"))
    )
    (net (code "42") (name "Net-(J2-PadB5)") (class "Default")
      (node (ref "J2") (pin "B5") (pinfunction "B5_B5") (pintype "bidirectional"))
      (node (ref "R2-USB2") (pin "1") (pinfunction "1_1") (pintype "passive"))
    )
    (net (code "43") (name "Net-(U5-PROG)") (class "Default")
      (node (ref "R2_BAT") (pin "2") (pinfunction "2_2") (pintype "passive"))
      (node (ref "U5") (pin "5") (pinfunction "PROG_5") (pintype "input"))
    )
    (net (code "44") (name "Net-(U5-STAT)") (class "Default")
      (node (ref "R1_BAT") (pin "1") (pinfunction "1_1") (pintype "passive"))
      (node (ref "U5") (pin "1") (pinfunction "STAT_1") (pintype "output"))
    )
    (net (code "45") (name "PREVGH") (class "Default")
      (node (ref "D5") (pin "1") (pinfunction "A_1") (pintype "bidirectional"))
      (node (ref "EDP_C9") (pin "1") (pinfunction "1_1") (pintype "passive"))
      (node (ref "J1") (pin "21") (pinfunction "21_21") (pintype "bidirectional"))
    )
    (net (code "46") (name "PREVGL") (class "Default")
      (node (ref "D4") (pin "2") (pinfunction "K_2") (pintype "bidirectional"))
      (node (ref "EDP_C11") (pin "1") (pinfunction "1_1") (pintype "passive"))
      (node (ref "J1") (pin "23") (pinfunction "23_23") (pintype "bidirectional"))
    )
    (net (code "47") (name "RESE") (class "Default")
      (node (ref "J1") (pin "3") (pinfunction "3_3") (pintype "bidirectional"))
      (node (ref "Q3") (pin "2") (pinfunction "S_2") (pintype "bidirectional"))
      (node (ref "R3") (pin "2") (pinfunction "2_2") (pintype "passive"))
    )
    (net (code "48") (name "RESE'") (class "Default")
      (node (ref "R2") (pin "2") (pinfunction "2_2") (pintype "passive"))
      (node (ref "R3") (pin "1") (pinfunction "1_1") (pintype "passive"))
      (node (ref "SJ1") (pin "2") (pinfunction "2_2") (pintype "passive"))
    )
    (net (code "49") (name "RESET") (class "Default")
      (node (ref "C5") (pin "1") (pinfunction "1_1") (pintype "passive"))
      (node (ref "IC1") (pin "1") (pinfunction "VOUT_1") (pintype "bidirectional"))
      (node (ref "RESET_BUTTON") (pin "3") (pinfunction "3_3") (pintype "passive"))
      (node (ref "RESET_BUTTON") (pin "4") (pinfunction "4_4") (pintype "passive"))
      (node (ref "R_RESET") (pin "2") (pinfunction "2_2") (pintype "passive"))
      (node (ref "U2") (pin "3") (pinfunction "EN_3") (pintype "input"))
    )
    (net (code "50") (name "RTC_RST") (class "Default")
      (node (ref "U2") (pin "16") (pinfunction "IO18_16") (pintype "bidirectional"))
      (node (ref "U3") (pin "4") (pinfunction "~{RST}_4") (pintype "input"))
    )
    (net (code "51") (name "RX") (class "Default")
      (node (ref "TP2") (pin "TP") (pinfunction "TP_TP") (pintype "input"))
      (node (ref "U2") (pin "24") (pinfunction "RXD0/GPIO17_24") (pintype "bidirectional"))
    )
    (net (code "52") (name "SCK") (class "Default")
      (node (ref "J1") (pin "13") (pinfunction "13_13") (pintype "bidirectional"))
      (node (ref "J4") (pin "P5") (pinfunction "CLK_P5") (pintype "bidirectional"))
      (node (ref "TP8") (pin "TP") (pinfunction "TP_TP") (pintype "input"))
      (node (ref "U1") (pin "6") (pinfunction "CLK_6") (pintype "input"))
      (node (ref "U2") (pin "6") (pinfunction "IO6_6") (pintype "bidirectional"))
    )
    (net (code "53") (name "SCL") (class "Default")
      (node (ref "J3") (pin "4") (pinfunction "4_4") (pintype "passive"))
      (node (ref "R2-PINH") (pin "1") (pinfunction "1_1") (pintype "passive"))
      (node (ref "R2-PINH1") (pin "1") (pinfunction "1_1") (pintype "passive"))
      (node (ref "SENSOR2") (pin "4") (pinfunction "SCK_4") (pintype "input"))
      (node (ref "U2") (pin "20") (pinfunction "IO22_20") (pintype "bidirectional"))
      (node (ref "U3") (pin "16") (pinfunction "SCL_16") (pintype "input"))
      (node (ref "U4") (pin "7") (pinfunction "SCL_7") (pintype "input"))
    )
    (net (code "54") (name "SDA") (class "Default")
      (node (ref "J3") (pin "3") (pinfunction "3_3") (pintype "passive"))
      (node (ref "R1-PINH") (pin "1") (pinfunction "1_1") (pintype "passive"))
      (node (ref "SENSOR2") (pin "3") (pinfunction "SDI_3") (pintype "bidirectional"))
      (node (ref "U2") (pin "19") (pinfunction "IO21_19") (pintype "bidirectional"))
      (node (ref "U3") (pin "15") (pinfunction "SDA_15") (pintype "bidirectional"))
      (node (ref "U4") (pin "8") (pinfunction "SDA_8") (pintype "bidirectional"))
    )
    (net (code "55") (name "SRC") (class "Default")
      (node (ref "C4") (pin "2") (pinfunction "2_2") (pintype "passive"))
      (node (ref "D5") (pin "2") (pinfunction "K_2") (pintype "bidirectional"))
      (node (ref "L1") (pin "1") (pinfunction "1_1") (pintype "passive"))
      (node (ref "Q3") (pin "3") (pinfunction "D_3") (pintype "bidirectional"))
    )
    (net (code "56") (name "SS_SD") (class "Default")
      (node (ref "J4") (pin "P2") (pinfunction "CD/DAT3_P2") (pintype "bidirectional"))
      (node (ref "U2") (pin "4") (pinfunction "IO4_4") (pintype "bidirectional"))
    )
    (net (code "57") (name "TX") (class "Default")
      (node (ref "TP1") (pin "TP") (pinfunction "TP_TP") (pintype "input"))
      (node (ref "U2") (pin "25") (pinfunction "TXD0/GPIO16_25") (pintype "bidirectional"))
    )
    (net (code "58") (name "USB_D+") (class "Default")
      (node (ref "D1") (pin "4") (pinfunction "I/O2_1_4") (pintype "bidirectional"))
      (node (ref "U2") (pin "14") (pinfunction "IO13_14") (pintype "bidirectional"))
    )
    (net (code "59") (name "USB_D-") (class "Default")
      (node (ref "D1") (pin "2") (pinfunction "I/O1_1_2") (pintype "bidirectional"))
      (node (ref "U2") (pin "13") (pinfunction "IO12_13") (pintype "bidirectional"))
    )
    (net (code "60") (name "VBAT") (class "Default")
      (node (ref "C2_BAT") (pin "1") (pinfunction "1_1") (pintype "passive"))
      (node (ref "Q1") (pin "1") (pinfunction "D_1") (pintype "bidirectional"))
      (node (ref "TP3") (pin "TP") (pinfunction "TP_TP") (pintype "input"))
      (node (ref "U4") (pin "2") (pinfunction "CELL_2") (pintype "power_in"))
      (node (ref "U4") (pin "3") (pinfunction "VDD_3") (pintype "power_in"))
      (node (ref "U5") (pin "3") (pinfunction "VBAT_3") (pintype "power_in"))
    )
    (net (code "61") (name "VBUS") (class "Default")
      (node (ref "C1_BAT") (pin "1") (pinfunction "1_1") (pintype "passive"))
      (node (ref "C4_USB") (pin "1") (pinfunction "1_1") (pintype "passive"))
      (node (ref "C5_USB") (pin "1") (pinfunction "1_1") (pintype "passive"))
      (node (ref "CHG_LED") (pin "A") (pinfunction "A_A") (pintype "passive"))
      (node (ref "D1") (pin "6") (pinfunction "VBUS_6") (pintype "bidirectional"))
      (node (ref "D2") (pin "1") (pinfunction "ANODE_1") (pintype "bidirectional"))
      (node (ref "PFMF.050.1") (pin "2") (pinfunction "2_2") (pintype "passive"))
      (node (ref "Q1") (pin "2") (pinfunction "G_2") (pintype "bidirectional"))
      (node (ref "R1_PWRUSB") (pin "2") (pinfunction "2_2") (pintype "passive"))
      (node (ref "TP14") (pin "TP") (pinfunction "TP_TP") (pintype "input"))
      (node (ref "U5") (pin "4") (pinfunction "VIN_4") (pintype "power_in"))
    )
    (net (code "62") (name "VRTC") (class "Default")
      (node (ref "C10_SUPERCAP") (pin "1") (pinfunction "1_1") (pintype "passive"))
      (node (ref "C8") (pin "1") (pinfunction "1_1") (pintype "passive"))
      (node (ref "R_CAPACITOR") (pin "1") (pinfunction "1_1") (pintype "passive"))
      (node (ref "U3") (pin "14") (pinfunction "VBAT_14") (pintype "power_in"))
    )
    (net (code "63") (name "VUSB") (class "Default")
      (node (ref "J2") (pin "A4") (pinfunction "A4_A4") (pintype "bidirectional"))
      (node (ref "J2") (pin "A9") (pinfunction "A9_A9") (pintype "bidirectional"))
      (node (ref "J2") (pin "B4") (pinfunction "B4_B4") (pintype "bidirectional"))
      (node (ref "J2") (pin "B9") (pinfunction "B9_B9") (pintype "bidirectional"))
      (node (ref "PFMF.050.1") (pin "1") (pinfunction "1_1") (pintype "passive"))
    )
    (net (code "64") (name "unconnected-(IC1-NC-Pad4)") (class "Default")
      (node (ref "IC1") (pin "4") (pinfunction "NC_4") (pintype "no_connect"))
    )
    (net (code "65") (name "unconnected-(IC4-NC-Pad4)") (class "Default")
      (node (ref "IC4") (pin "4") (pinfunction "NC_4") (pintype "no_connect"))
    )
    (net (code "66") (name "unconnected-(J1-Pad1)") (class "Default")
      (node (ref "J1") (pin "1") (pinfunction "1_1") (pintype "bidirectional"))
    )
    (net (code "67") (name "unconnected-(J1-Pad6)") (class "Default")
      (node (ref "J1") (pin "6") (pinfunction "6_6") (pintype "bidirectional"))
    )
    (net (code "68") (name "unconnected-(J1-Pad7)") (class "Default")
      (node (ref "J1") (pin "7") (pinfunction "7_7") (pintype "bidirectional"))
    )
    (net (code "69") (name "unconnected-(J2-PadA8)") (class "Default")
      (node (ref "J2") (pin "A8") (pinfunction "A8_A8") (pintype "bidirectional"))
    )
    (net (code "70") (name "unconnected-(J2-PadB8)") (class "Default")
      (node (ref "J2") (pin "B8") (pinfunction "B8_B8") (pintype "bidirectional"))
    )
    (net (code "71") (name "unconnected-(J4-DAT1-PadP8)") (class "Default")
      (node (ref "J4") (pin "P8") (pinfunction "DAT1_P8") (pintype "bidirectional"))
    )
    (net (code "72") (name "unconnected-(J4-DAT2-PadP1)") (class "Default")
      (node (ref "J4") (pin "P1") (pinfunction "DAT2_P1") (pintype "bidirectional"))
    )
    (net (code "73") (name "unconnected-(J4-DETECTION_1-PadS1)") (class "Default")
      (node (ref "J4") (pin "S1") (pinfunction "DETECTION_1_S1") (pintype "bidirectional"))
    )
    (net (code "74") (name "unconnected-(J4-DETECTION_2-PadS2)") (class "Default")
      (node (ref "J4") (pin "S2") (pinfunction "DETECTION_2_S2") (pintype "bidirectional"))
    )
    (net (code "75") (name "unconnected-(U2-NC-Pad22)") (class "Default")
      (node (ref "U2") (pin "22") (pinfunction "NC_22") (pintype "no_connect"))
    )
    (net (code "76") (name "unconnected-(U4-~{ALERT}-Pad5)") (class "Default")
      (node (ref "U4") (pin "5") (pinfunction "~{ALERT}_5") (pintype "output"))
    )
  )
)
